# Isolated_Output.net
KiCad netlist of a schematic drawn in Altium Designer
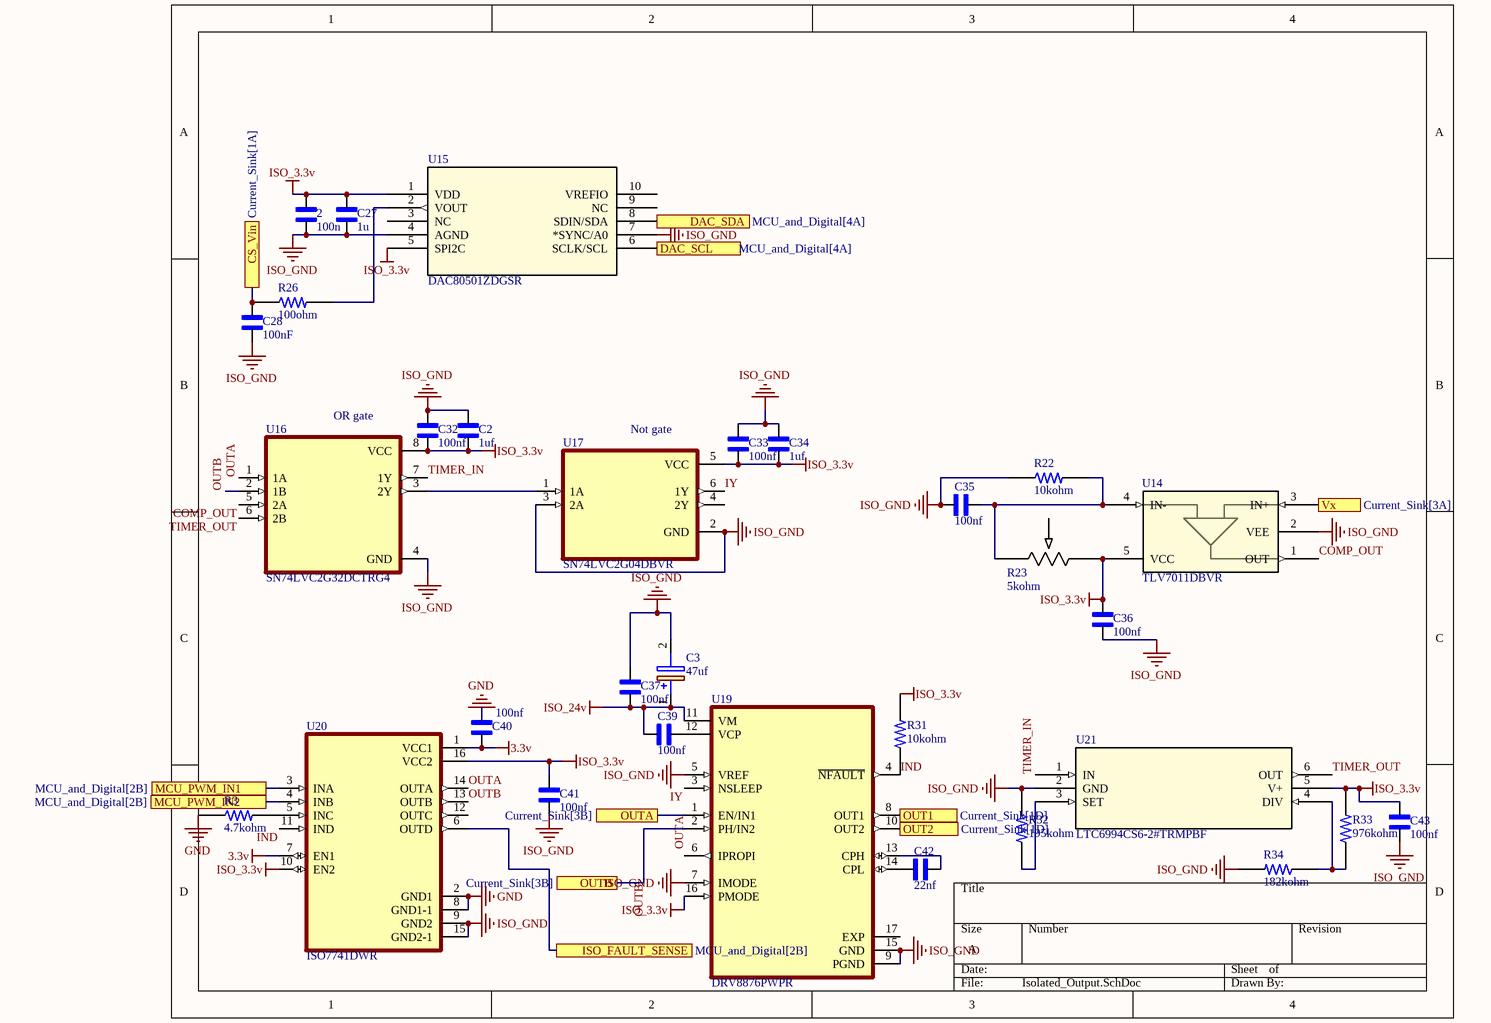
[diagram p0: Isolated_Output.SchDoc]

(export (version "E")
  (design (tool "Eeschema 10.0.6"))
  (components
    (comp (ref "2")
      (value "100n")
      (footprint "CAPC1608X90")
      (description "0603 1 nF 50 V Â±10 % Tolerance X7R Surface Mount Ceramic Capacitor")
      (fields (field (name "MF") "Yageo") (field (name "MP") "C0603KRX7R9BB102"))
      (libsource (lib "C0603KRX7R9BB102") (part "C0603KRX7R9BB102"))
    )
    (comp (ref "C2")
      (value "1uf")
      (footprint "CAPC1608X90")
      (description "0603 1 nF 50 V Â±10 % Tolerance X7R Surface Mount Ceramic Capacitor")
      (fields (field (name "MF") "Yageo") (field (name "MP") "C0603KRX7R9BB102"))
      (libsource (lib "") (part "C0603KRX7R9BB102_3"))
    )
    (comp (ref "C3")
      (value "47uf")
      (footprint "SamacSys:CAPAE660X800N")
      (description "Capacitor Polarised")
      (fields (field (name "MANUFACTURER_PART_NUMBER") "GYF1H470MCQ1GS"))
      (libsource (lib "*") (part "GYF1H470MCQ1GS"))
    )
    (comp (ref "C27")
      (value "1u")
      (footprint "CAPC1608X90")
      (description "0603 1 nF 50 V Â±10 % Tolerance X7R Surface Mount Ceramic Capacitor")
      (fields (field (name "MF") "Yageo") (field (name "MP") "C0603KRX7R9BB102"))
      (libsource (lib "C0603KRX7R9BB102") (part "C0603KRX7R9BB102"))
    )
    (comp (ref "C28")
      (value "100nF")
      (footprint "CAPC1608X90")
      (description "0603 1 nF 50 V Â±10 % Tolerance X7R Surface Mount Ceramic Capacitor")
      (fields (field (name "MF") "Yageo") (field (name "MP") "C0603KRX7R9BB102"))
      (libsource (lib "C0603KRX7R9BB102") (part "C0603KRX7R9BB102"))
    )
    (comp (ref "C32")
      (value "100nf")
      (footprint "CAPC1608X90")
      (description "0603 1 nF 50 V Â±10 % Tolerance X7R Surface Mount Ceramic Capacitor")
      (fields (field (name "MF") "Yageo") (field (name "MP") "C0603KRX7R9BB102"))
      (libsource (lib "") (part "C0603KRX7R9BB102_3"))
    )
    (comp (ref "C33")
      (value "100nf")
      (footprint "CAPC1608X90")
      (description "0603 1 nF 50 V Â±10 % Tolerance X7R Surface Mount Ceramic Capacitor")
      (fields (field (name "MF") "Yageo") (field (name "MP") "C0603KRX7R9BB102"))
      (libsource (lib "") (part "C0603KRX7R9BB102_3"))
    )
    (comp (ref "C34")
      (value "1uf")
      (footprint "CAPC1608X90")
      (description "0603 1 nF 50 V Â±10 % Tolerance X7R Surface Mount Ceramic Capacitor")
      (fields (field (name "MF") "Yageo") (field (name "MP") "C0603KRX7R9BB102"))
      (libsource (lib "") (part "C0603KRX7R9BB102_3"))
    )
    (comp (ref "C35")
      (value "100nf")
      (footprint "CAPC1608X90")
      (description "0603 1 nF 50 V Â±10 % Tolerance X7R Surface Mount Ceramic Capacitor")
      (fields (field (name "MF") "Yageo") (field (name "MP") "C0603KRX7R9BB102"))
      (libsource (lib "") (part "C0603KRX7R9BB102_2"))
    )
    (comp (ref "C36")
      (value "100nf")
      (footprint "CAPC1608X90")
      (description "0603 1 nF 50 V Â±10 % Tolerance X7R Surface Mount Ceramic Capacitor")
      (fields (field (name "MF") "Yageo") (field (name "MP") "C0603KRX7R9BB102"))
      (libsource (lib "") (part "C0603KRX7R9BB102_3"))
    )
    (comp (ref "C37")
      (value "100nf")
      (footprint "CAPC1608X90")
      (description "0603 1 nF 50 V Â±10 % Tolerance X7R Surface Mount Ceramic Capacitor")
      (fields (field (name "MF") "Yageo") (field (name "MP") "C0603KRX7R9BB102"))
      (libsource (lib "C0603KRX7R9BB102") (part "C0603KRX7R9BB102"))
    )
    (comp (ref "C39")
      (value "100nf")
      (footprint "CAPC1608X90")
      (description "0603 1 nF 50 V Â±10 % Tolerance X7R Surface Mount Ceramic Capacitor")
      (fields (field (name "MF") "Yageo") (field (name "MP") "C0603KRX7R9BB102"))
      (libsource (lib "") (part "C0603KRX7R9BB102_1"))
    )
    (comp (ref "C40")
      (value "100nf")
      (footprint "CAPC1608X90")
      (description "0603 1 nF 50 V Â±10 % Tolerance X7R Surface Mount Ceramic Capacitor")
      (fields (field (name "MF") "Yageo") (field (name "MP") "C0603KRX7R9BB102"))
      (libsource (lib "C0603KRX7R9BB102") (part "C0603KRX7R9BB102"))
    )
    (comp (ref "C41")
      (value "100nf")
      (footprint "CAPC1608X90")
      (description "0603 1 nF 50 V Â±10 % Tolerance X7R Surface Mount Ceramic Capacitor")
      (fields (field (name "MF") "Yageo") (field (name "MP") "C0603KRX7R9BB102"))
      (libsource (lib "C0603KRX7R9BB102") (part "C0603KRX7R9BB102"))
    )
    (comp (ref "C42")
      (value "22nf")
      (footprint "CAPC1608X90")
      (description "0603 1 nF 50 V Â±10 % Tolerance X7R Surface Mount Ceramic Capacitor")
      (fields (field (name "MF") "Yageo") (field (name "MP") "C0603KRX7R9BB102"))
      (libsource (lib "") (part "C0603KRX7R9BB102_1"))
    )
    (comp (ref "C43")
      (value "100nf")
      (footprint "CAPC1608X90")
      (description "0603 1 nF 50 V Â±10 % Tolerance X7R Surface Mount Ceramic Capacitor")
      (fields (field (name "MF") "Yageo") (field (name "MP") "C0603KRX7R9BB102"))
      (libsource (lib "C0603KRX7R9BB102") (part "C0603KRX7R9BB102"))
    )
    (comp (ref "R3")
      (value "4.7kohm")
      (footprint "RESC1607X60N")
      (description "10 kOhms Â±5% 0.1W, 1/10W Chip Resistor 0603 (1608 Metric) Moisture Resistant Thick Film")
      (fields (field (name "MF") "Yageo") (field (name "MP") "RC0603JR-0710KL"))
      (libsource (lib "RC0603JR-0710KL") (part "RC0603JR-0710KL"))
    )
    (comp (ref "R22")
      (value "10kohm")
      (footprint "RESC1607X60N")
      (description "10 kOhms Â±5% 0.1W, 1/10W Chip Resistor 0603 (1608 Metric) Moisture Resistant Thick Film")
      (fields (field (name "MF") "Yageo") (field (name "MP") "RC0603JR-0710KL"))
      (libsource (lib "RC0603JR-0710KL") (part "RC0603JR-0710KL"))
    )
    (comp (ref "R23")
      (value "5kohm")
      (footprint "POT_T93XA_VIS")
      (description "T93 XA 100K 10% TU50 e3")
      (fields
        (field (name "MANUFACTURER_PART_NUMBER") "T93XA104KT20")
        (field (name "COPYRIGHT") "Copyright (C) 2026 Ultra Librarian. All rights reserved.")
      )
      (libsource (lib "T93XA104KT20") (part "T93XA104KT20"))
    )
    (comp (ref "R26")
      (value "100ohm")
      (footprint "RESC1607X60N")
      (description "10 kOhms Â±5% 0.1W, 1/10W Chip Resistor 0603 (1608 Metric) Moisture Resistant Thick Film")
      (fields (field (name "MF") "Yageo") (field (name "MP") "RC0603JR-0710KL"))
      (libsource (lib "RC0603JR-0710KL") (part "RC0603JR-0710KL"))
    )
    (comp (ref "R31")
      (value "10kohm")
      (footprint "RESC1607X60N")
      (description "10 kOhms Â±5% 0.1W, 1/10W Chip Resistor 0603 (1608 Metric) Moisture Resistant Thick Film")
      (fields (field (name "MF") "Yageo") (field (name "MP") "RC0603JR-0710KL"))
      (libsource (lib "RC0603JR-0710KL") (part "RC0603JR-0710KL"))
    )
    (comp (ref "R32")
      (value "195kohm")
      (footprint "RESC1607X60N")
      (description "10 kOhms Â±5% 0.1W, 1/10W Chip Resistor 0603 (1608 Metric) Moisture Resistant Thick Film")
      (fields (field (name "MF") "Yageo") (field (name "MP") "RC0603JR-0710KL"))
      (libsource (lib "RC0603JR-0710KL") (part "RC0603JR-0710KL"))
    )
    (comp (ref "R33")
      (value "976kohm")
      (footprint "RESC1607X60N")
      (description "10 kOhms Â±5% 0.1W, 1/10W Chip Resistor 0603 (1608 Metric) Moisture Resistant Thick Film")
      (fields (field (name "MF") "Yageo") (field (name "MP") "RC0603JR-0710KL"))
      (libsource (lib "RC0603JR-0710KL") (part "RC0603JR-0710KL"))
    )
    (comp (ref "R34")
      (value "182kohm")
      (footprint "RESC1607X60N")
      (description "10 kOhms Â±5% 0.1W, 1/10W Chip Resistor 0603 (1608 Metric) Moisture Resistant Thick Film")
      (fields (field (name "MF") "Yageo") (field (name "MP") "RC0603JR-0710KL"))
      (libsource (lib "RC0603JR-0710KL") (part "RC0603JR-0710KL"))
    )
    (comp (ref "U14")
      (value "TLV7011DBVR")
      (footprint "SOT_1DBVR_TEX")
      (description "Low power, small size comparator with push-pull output 5-SOT-23 -40 to 125")
      (fields (field (name "COPYRIGHT") "Copyright (C) 2026 Ultra Librarian. All rights reserved."))
      (libsource (lib "TLV7011DBVR") (part "TLV7011DBVR"))
    )
    (comp (ref "U15")
      (value "DAC80501ZDGSR")
      (footprint "DGS10_TEX")
      (fields (field (name "COPYRIGHT") "Copyright (C) 2025 Ultra Librarian. All rights reserved."))
      (libsource (lib "DAC80501ZDGSR") (part "DAC80501ZDGSR"))
    )
    (comp (ref "U16")
      (value "SN74LVC2G32DCTRG4")
      (footprint "SOP65P400X130-8N")
      (description "Dual 2-Input Positive-OR Gate 8-SM8 -40 to 125")
      (fields (field (name "MF") "Texas Instruments"))
      (libsource (lib "SN74LVC2G32DCTRG4") (part "SN74LVC2G32DCTRG4"))
    )
    (comp (ref "U17")
      (value "SN74LVC2G04DBVR")
      (footprint "SOT95P280X145-6N")
      (description "2-ch, 1.65-V to 5.5-V inverters")
      (fields (field (name "MF") "Texas Instruments"))
      (libsource (lib "SN74LVC2G04DBVR") (part "SN74LVC2G04DBVR"))
    )
    (comp (ref "U19")
      (value "DRV8876PWPR")
      (footprint "IC_DRV8876PWPR")
      (description "40-V, 3.5-A H-bridge motor driver with integrated current sensing & current-sense feedback")
      (fields (field (name "MF") "Texas Instruments"))
      (libsource (lib "DRV8876PWPR") (part "DRV8876PWPR"))
    )
    (comp (ref "U20")
      (value "ISO7741DWR")
      (footprint "SOIC127P1030X265-16N")
      (description "Robust EMC, quad-channel, 3/1, reinforced digital isolator")
      (fields (field (name "MF") "Texas Instruments"))
      (libsource (lib "ISO7741DWR") (part "ISO7741DWR"))
    )
    (comp (ref "U21")
      (value "LTC6994CS6-2#TRMPBF")
      (footprint "TSOT-23_S6_LIT")
      (description "Description")
      (fields (field (name "COPYRIGHT") "Copyright (C) 2025 Ultra Librarian. All rights reserved."))
      (libsource (lib "LTC6994CS6-2TRMPBF") (part "LTC6994CS6-2TRMPBF"))
    )
  )
  (nets
    (net (code "1") (name "/COMP_OUT") (class "Default")
      (node (ref "U14") (pin "1") (pinfunction "OUT_1") (pintype "output"))
      (node (ref "U16") (pin "5") (pinfunction "2A_5") (pintype "input"))
    )
    (net (code "2") (name "/CS_Vin") (class "Default")
      (node (ref "C28") (pin "1") (pinfunction "1_1") (pintype "passive"))
      (node (ref "R26") (pin "1") (pinfunction "1_1") (pintype "passive"))
    )
    (net (code "3") (name "/DAC_SCL") (class "Default")
      (node (ref "U15") (pin "6") (pinfunction "SCLK/SCL_6") (pintype "passive"))
    )
    (net (code "4") (name "/DAC_SDA") (class "Default")
      (node (ref "U15") (pin "8") (pinfunction "SDIN/SDA_8") (pintype "passive"))
    )
    (net (code "5") (name "/IND") (class "Default")
      (node (ref "R31") (pin "1") (pinfunction "1_1") (pintype "passive"))
      (node (ref "U19") (pin "4") (pinfunction "~{NFAULT}_4") (pintype "output"))
      (node (ref "U20") (pin "11") (pinfunction "IND_11") (pintype "input"))
    )
    (net (code "6") (name "/ISO_FAULT_SENSE") (class "Default")
      (node (ref "U20") (pin "6") (pinfunction "OUTD_6") (pintype "output"))
    )
    (net (code "7") (name "/IY") (class "Default")
      (node (ref "U17") (pin "6") (pinfunction "1Y_6") (pintype "output"))
      (node (ref "U19") (pin "3") (pinfunction "NSLEEP_3") (pintype "input"))
    )
    (net (code "8") (name "/MCU_PWM_IN1") (class "Default")
      (node (ref "U20") (pin "3") (pinfunction "INA_3") (pintype "input"))
    )
    (net (code "9") (name "/MCU_PWM_IN2") (class "Default")
      (node (ref "U20") (pin "4") (pinfunction "INB_4") (pintype "input"))
    )
    (net (code "10") (name "/OUT1") (class "Default")
      (node (ref "U19") (pin "8") (pinfunction "OUT1_8") (pintype "output"))
    )
    (net (code "11") (name "/OUT2") (class "Default")
      (node (ref "U19") (pin "10") (pinfunction "OUT2_10") (pintype "output"))
    )
    (net (code "12") (name "/OUTA") (class "Default")
      (node (ref "U16") (pin "1") (pinfunction "1A_1") (pintype "input"))
      (node (ref "U19") (pin "1") (pinfunction "EN/IN1_1") (pintype "input"))
      (node (ref "U20") (pin "14") (pinfunction "OUTA_14") (pintype "output"))
    )
    (net (code "13") (name "/OUTB") (class "Default")
      (node (ref "U16") (pin "2") (pinfunction "1B_2") (pintype "input"))
      (node (ref "U19") (pin "2") (pinfunction "PH/IN2_2") (pintype "input"))
      (node (ref "U20") (pin "13") (pinfunction "OUTB_13") (pintype "output"))
    )
    (net (code "14") (name "/TIMER_IN") (class "Default")
      (node (ref "U16") (pin "7") (pinfunction "1Y_7") (pintype "output"))
      (node (ref "U21") (pin "1") (pinfunction "IN_1") (pintype "input"))
    )
    (net (code "15") (name "/TIMER_OUT") (class "Default")
      (node (ref "U16") (pin "6") (pinfunction "2B_6") (pintype "input"))
      (node (ref "U21") (pin "6") (pinfunction "OUT_6") (pintype "output"))
    )
    (net (code "16") (name "/Vx") (class "Default")
      (node (ref "U14") (pin "3") (pinfunction "IN+_3") (pintype "input"))
    )
    (net (code "17") (name "3.3v") (class "Default")
      (node (ref "C40") (pin "2") (pinfunction "2_2") (pintype "passive"))
      (node (ref "U20") (pin "1") (pinfunction "VCC1_1") (pintype "power_in"))
      (node (ref "U20") (pin "7") (pinfunction "EN1_7") (pintype "bidirectional"))
    )
    (net (code "18") (name "GND") (class "Default")
      (node (ref "C40") (pin "1") (pinfunction "1_1") (pintype "passive"))
      (node (ref "R3") (pin "1") (pinfunction "1_1") (pintype "passive"))
      (node (ref "U20") (pin "2") (pinfunction "GND1_2") (pintype "power_in"))
      (node (ref "U20") (pin "8") (pinfunction "GND1-1_8") (pintype "power_in"))
    )
    (net (code "19") (name "ISO_3.3v") (class "Default")
      (node (ref "2") (pin "1") (pinfunction "1_1") (pintype "passive"))
      (node (ref "C2") (pin "1") (pinfunction "1_1") (pintype "passive"))
      (node (ref "C27") (pin "1") (pinfunction "1_1") (pintype "passive"))
      (node (ref "C32") (pin "1") (pinfunction "1_1") (pintype "passive"))
      (node (ref "C33") (pin "1") (pinfunction "1_1") (pintype "passive"))
      (node (ref "C34") (pin "1") (pinfunction "1_1") (pintype "passive"))
      (node (ref "C36") (pin "2") (pinfunction "2_2") (pintype "passive"))
      (node (ref "C41") (pin "1") (pinfunction "1_1") (pintype "passive"))
      (node (ref "C43") (pin "1") (pinfunction "1_1") (pintype "passive"))
      (node (ref "R23") (pin "3") (pinfunction "3_3") (pintype "passive"))
      (node (ref "R31") (pin "2") (pinfunction "2_2") (pintype "passive"))
      (node (ref "R33") (pin "2") (pinfunction "2_2") (pintype "passive"))
      (node (ref "U14") (pin "5") (pinfunction "VCC_5") (pintype "power_in"))
      (node (ref "U15") (pin "1") (pinfunction "VDD_1") (pintype "power_in"))
      (node (ref "U15") (pin "5") (pinfunction "SPI2C_5") (pintype "passive"))
      (node (ref "U16") (pin "8") (pinfunction "VCC_8") (pintype "power_in"))
      (node (ref "U17") (pin "5") (pinfunction "VCC_5") (pintype "power_in"))
      (node (ref "U19") (pin "16") (pinfunction "PMODE_16") (pintype "input"))
      (node (ref "U20") (pin "10") (pinfunction "EN2_10") (pintype "bidirectional"))
      (node (ref "U20") (pin "16") (pinfunction "VCC2_16") (pintype "power_in"))
      (node (ref "U21") (pin "5") (pinfunction "V+_5") (pintype "power_in"))
    )
    (net (code "20") (name "ISO_24v") (class "Default")
      (node (ref "C3") (pin "1") (pinfunction "+_1") (pintype "passive"))
      (node (ref "C37") (pin "2") (pinfunction "2_2") (pintype "passive"))
      (node (ref "C39") (pin "2") (pinfunction "2_2") (pintype "passive"))
      (node (ref "U19") (pin "11") (pinfunction "VM_11") (pintype "power_in"))
    )
    (net (code "21") (name "ISO_GND") (class "Default")
      (node (ref "2") (pin "2") (pinfunction "2_2") (pintype "passive"))
      (node (ref "C2") (pin "2") (pinfunction "2_2") (pintype "passive"))
      (node (ref "C27") (pin "2") (pinfunction "2_2") (pintype "passive"))
      (node (ref "C28") (pin "2") (pinfunction "2_2") (pintype "passive"))
      (node (ref "C3") (pin "2") (pinfunction "-_2") (pintype "passive"))
      (node (ref "C32") (pin "2") (pinfunction "2_2") (pintype "passive"))
      (node (ref "C33") (pin "2") (pinfunction "2_2") (pintype "passive"))
      (node (ref "C34") (pin "2") (pinfunction "2_2") (pintype "passive"))
      (node (ref "C35") (pin "1") (pinfunction "1_1") (pintype "passive"))
      (node (ref "C36") (pin "1") (pinfunction "1_1") (pintype "passive"))
      (node (ref "C37") (pin "1") (pinfunction "1_1") (pintype "passive"))
      (node (ref "C41") (pin "2") (pinfunction "2_2") (pintype "passive"))
      (node (ref "C43") (pin "2") (pinfunction "2_2") (pintype "passive"))
      (node (ref "R22") (pin "1") (pinfunction "1_1") (pintype "passive"))
      (node (ref "R32") (pin "2") (pinfunction "2_2") (pintype "passive"))
      (node (ref "R34") (pin "2") (pinfunction "2_2") (pintype "passive"))
      (node (ref "U14") (pin "2") (pinfunction "VEE_2") (pintype "power_in"))
      (node (ref "U15") (pin "4") (pinfunction "AGND_4") (pintype "power_in"))
      (node (ref "U15") (pin "7") (pinfunction "*SYNC/A0_7") (pintype "passive"))
      (node (ref "U16") (pin "4") (pinfunction "GND_4") (pintype "power_in"))
      (node (ref "U17") (pin "2") (pinfunction "GND_2") (pintype "power_in"))
      (node (ref "U17") (pin "3") (pinfunction "2A_3") (pintype "input"))
      (node (ref "U19") (pin "15") (pinfunction "GND_15") (pintype "power_in"))
      (node (ref "U19") (pin "5") (pinfunction "VREF_5") (pintype "input"))
      (node (ref "U19") (pin "7") (pinfunction "IMODE_7") (pintype "input"))
      (node (ref "U19") (pin "9") (pinfunction "PGND_9") (pintype "power_in"))
      (node (ref "U20") (pin "15") (pinfunction "GND2-1_15") (pintype "power_in"))
      (node (ref "U20") (pin "9") (pinfunction "GND2_9") (pintype "power_in"))
      (node (ref "U21") (pin "2") (pinfunction "GND_2") (pintype "power_in"))
    )
    (net (code "22") (name "Net-(U14-IN-)") (class "Default")
      (node (ref "C35") (pin "2") (pinfunction "2_2") (pintype "passive"))
      (node (ref "R22") (pin "2") (pinfunction "2_2") (pintype "passive"))
      (node (ref "R23") (pin "1") (pinfunction "1_1") (pintype "passive"))
      (node (ref "U14") (pin "4") (pinfunction "IN-_4") (pintype "input"))
    )
    (net (code "23") (name "Net-(U15-VOUT)") (class "Default")
      (node (ref "R26") (pin "2") (pinfunction "2_2") (pintype "passive"))
      (node (ref "U15") (pin "2") (pinfunction "VOUT_2") (pintype "output"))
    )
    (net (code "24") (name "Net-(U16-2Y)") (class "Default")
      (node (ref "U16") (pin "3") (pinfunction "2Y_3") (pintype "output"))
      (node (ref "U17") (pin "1") (pinfunction "1A_1") (pintype "input"))
    )
    (net (code "25") (name "Net-(U19-CPH)") (class "Default")
      (node (ref "C42") (pin "1") (pinfunction "1_1") (pintype "passive"))
      (node (ref "U19") (pin "13") (pinfunction "CPH_13") (pintype "bidirectional"))
    )
    (net (code "26") (name "Net-(U19-CPL)") (class "Default")
      (node (ref "C42") (pin "2") (pinfunction "2_2") (pintype "passive"))
      (node (ref "U19") (pin "14") (pinfunction "CPL_14") (pintype "bidirectional"))
    )
    (net (code "27") (name "Net-(U19-VCP)") (class "Default")
      (node (ref "C39") (pin "1") (pinfunction "1_1") (pintype "passive"))
      (node (ref "U19") (pin "12") (pinfunction "VCP_12") (pintype "power_in"))
    )
    (net (code "28") (name "Net-(U20-INC)") (class "Default")
      (node (ref "R3") (pin "2") (pinfunction "2_2") (pintype "passive"))
      (node (ref "U20") (pin "5") (pinfunction "INC_5") (pintype "input"))
    )
    (net (code "29") (name "Net-(U21-DIV)") (class "Default")
      (node (ref "R33") (pin "1") (pinfunction "1_1") (pintype "passive"))
      (node (ref "R34") (pin "1") (pinfunction "1_1") (pintype "passive"))
      (node (ref "U21") (pin "4") (pinfunction "DIV_4") (pintype "input"))
    )
    (net (code "30") (name "Net-(U21-SET)") (class "Default")
      (node (ref "R32") (pin "1") (pinfunction "1_1") (pintype "passive"))
      (node (ref "U21") (pin "3") (pinfunction "SET_3") (pintype "input"))
    )
    (net (code "31") (name "unconnected-(R23-Pad2)") (class "Default")
      (node (ref "R23") (pin "2") (pinfunction "2_2") (pintype "passive"))
    )
    (net (code "32") (name "unconnected-(U15-NC-Pad3)") (class "Default")
      (node (ref "U15") (pin "3") (pinfunction "NC_3") (pintype "passive"))
    )
    (net (code "33") (name "unconnected-(U15-NC-Pad9)") (class "Default")
      (node (ref "U15") (pin "9") (pinfunction "NC_9") (pintype "passive"))
    )
    (net (code "34") (name "unconnected-(U15-VREFIO-Pad10)") (class "Default")
      (node (ref "U15") (pin "10") (pinfunction "VREFIO_10") (pintype "power_in"))
    )
    (net (code "35") (name "unconnected-(U17-2Y-Pad4)") (class "Default")
      (node (ref "U17") (pin "4") (pinfunction "2Y_4") (pintype "output"))
    )
    (net (code "36") (name "unconnected-(U19-EXP-Pad17)") (class "Default")
      (node (ref "U19") (pin "17") (pinfunction "EXP_17") (pintype "passive"))
    )
    (net (code "37") (name "unconnected-(U19-IPROPI-Pad6)") (class "Default")
      (node (ref "U19") (pin "6") (pinfunction "IPROPI_6") (pintype "output"))
    )
    (net (code "38") (name "unconnected-(U20-OUTC-Pad12)") (class "Default")
      (node (ref "U20") (pin "12") (pinfunction "OUTC_12") (pintype "output"))
    )
  )
)
